# dw1000_schematic.net
KiCad netlist of a schematic drawn in EAGLE
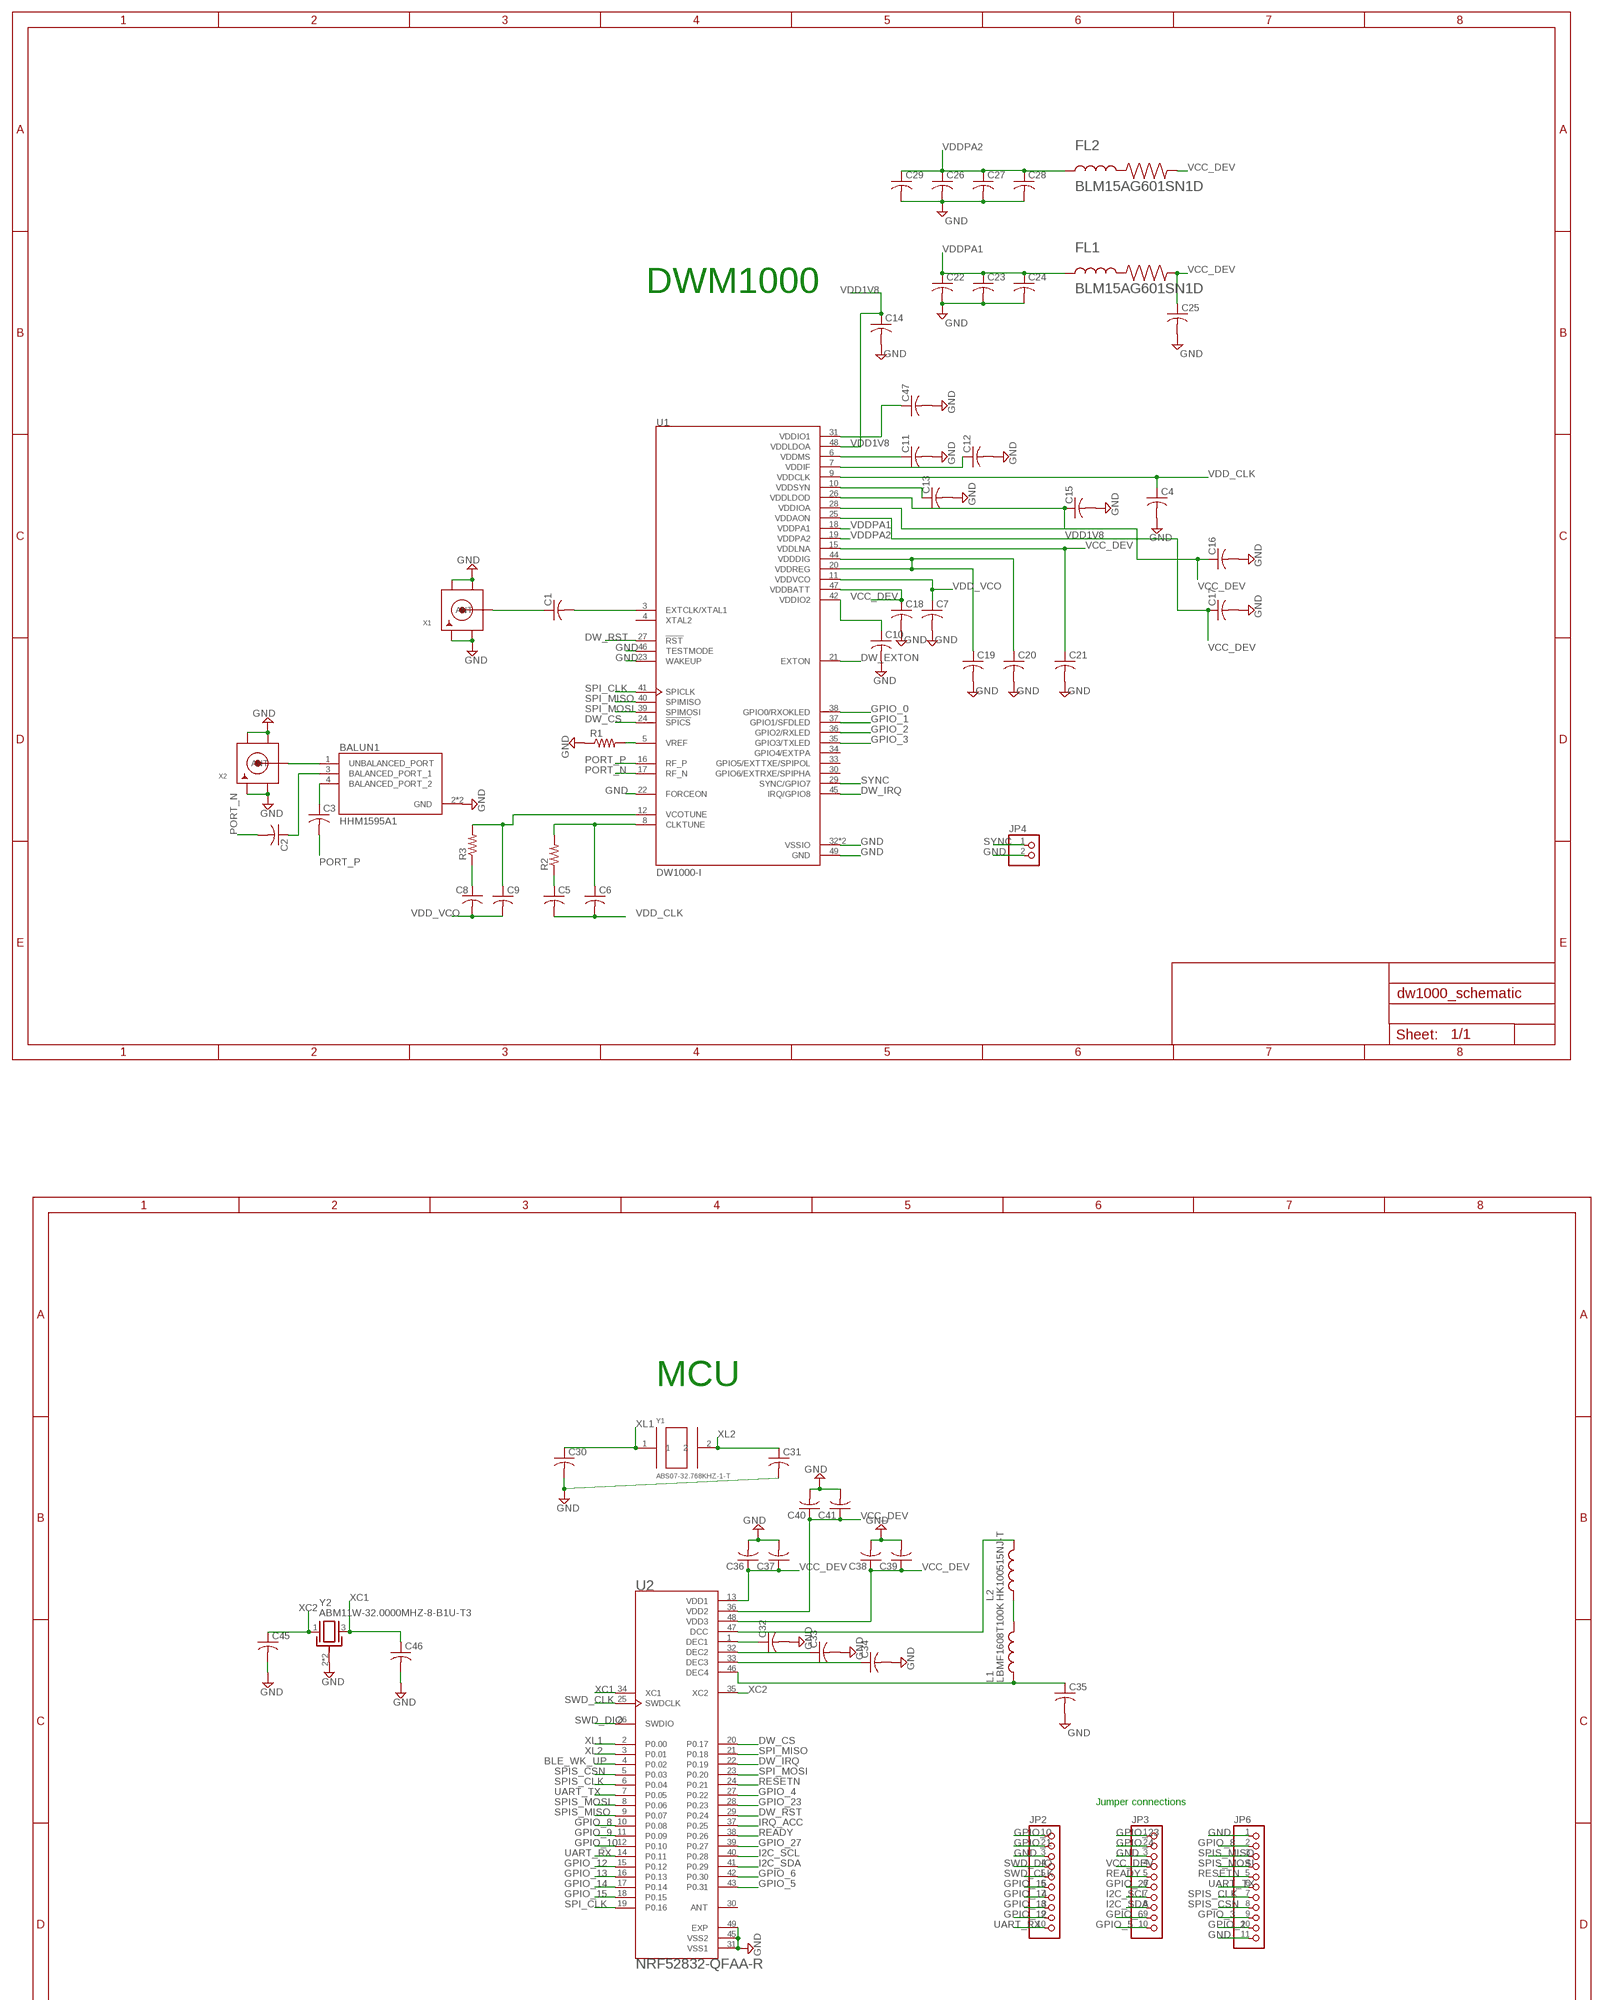
[diagram p0: schematic, sheet 1, part 1 of 2]
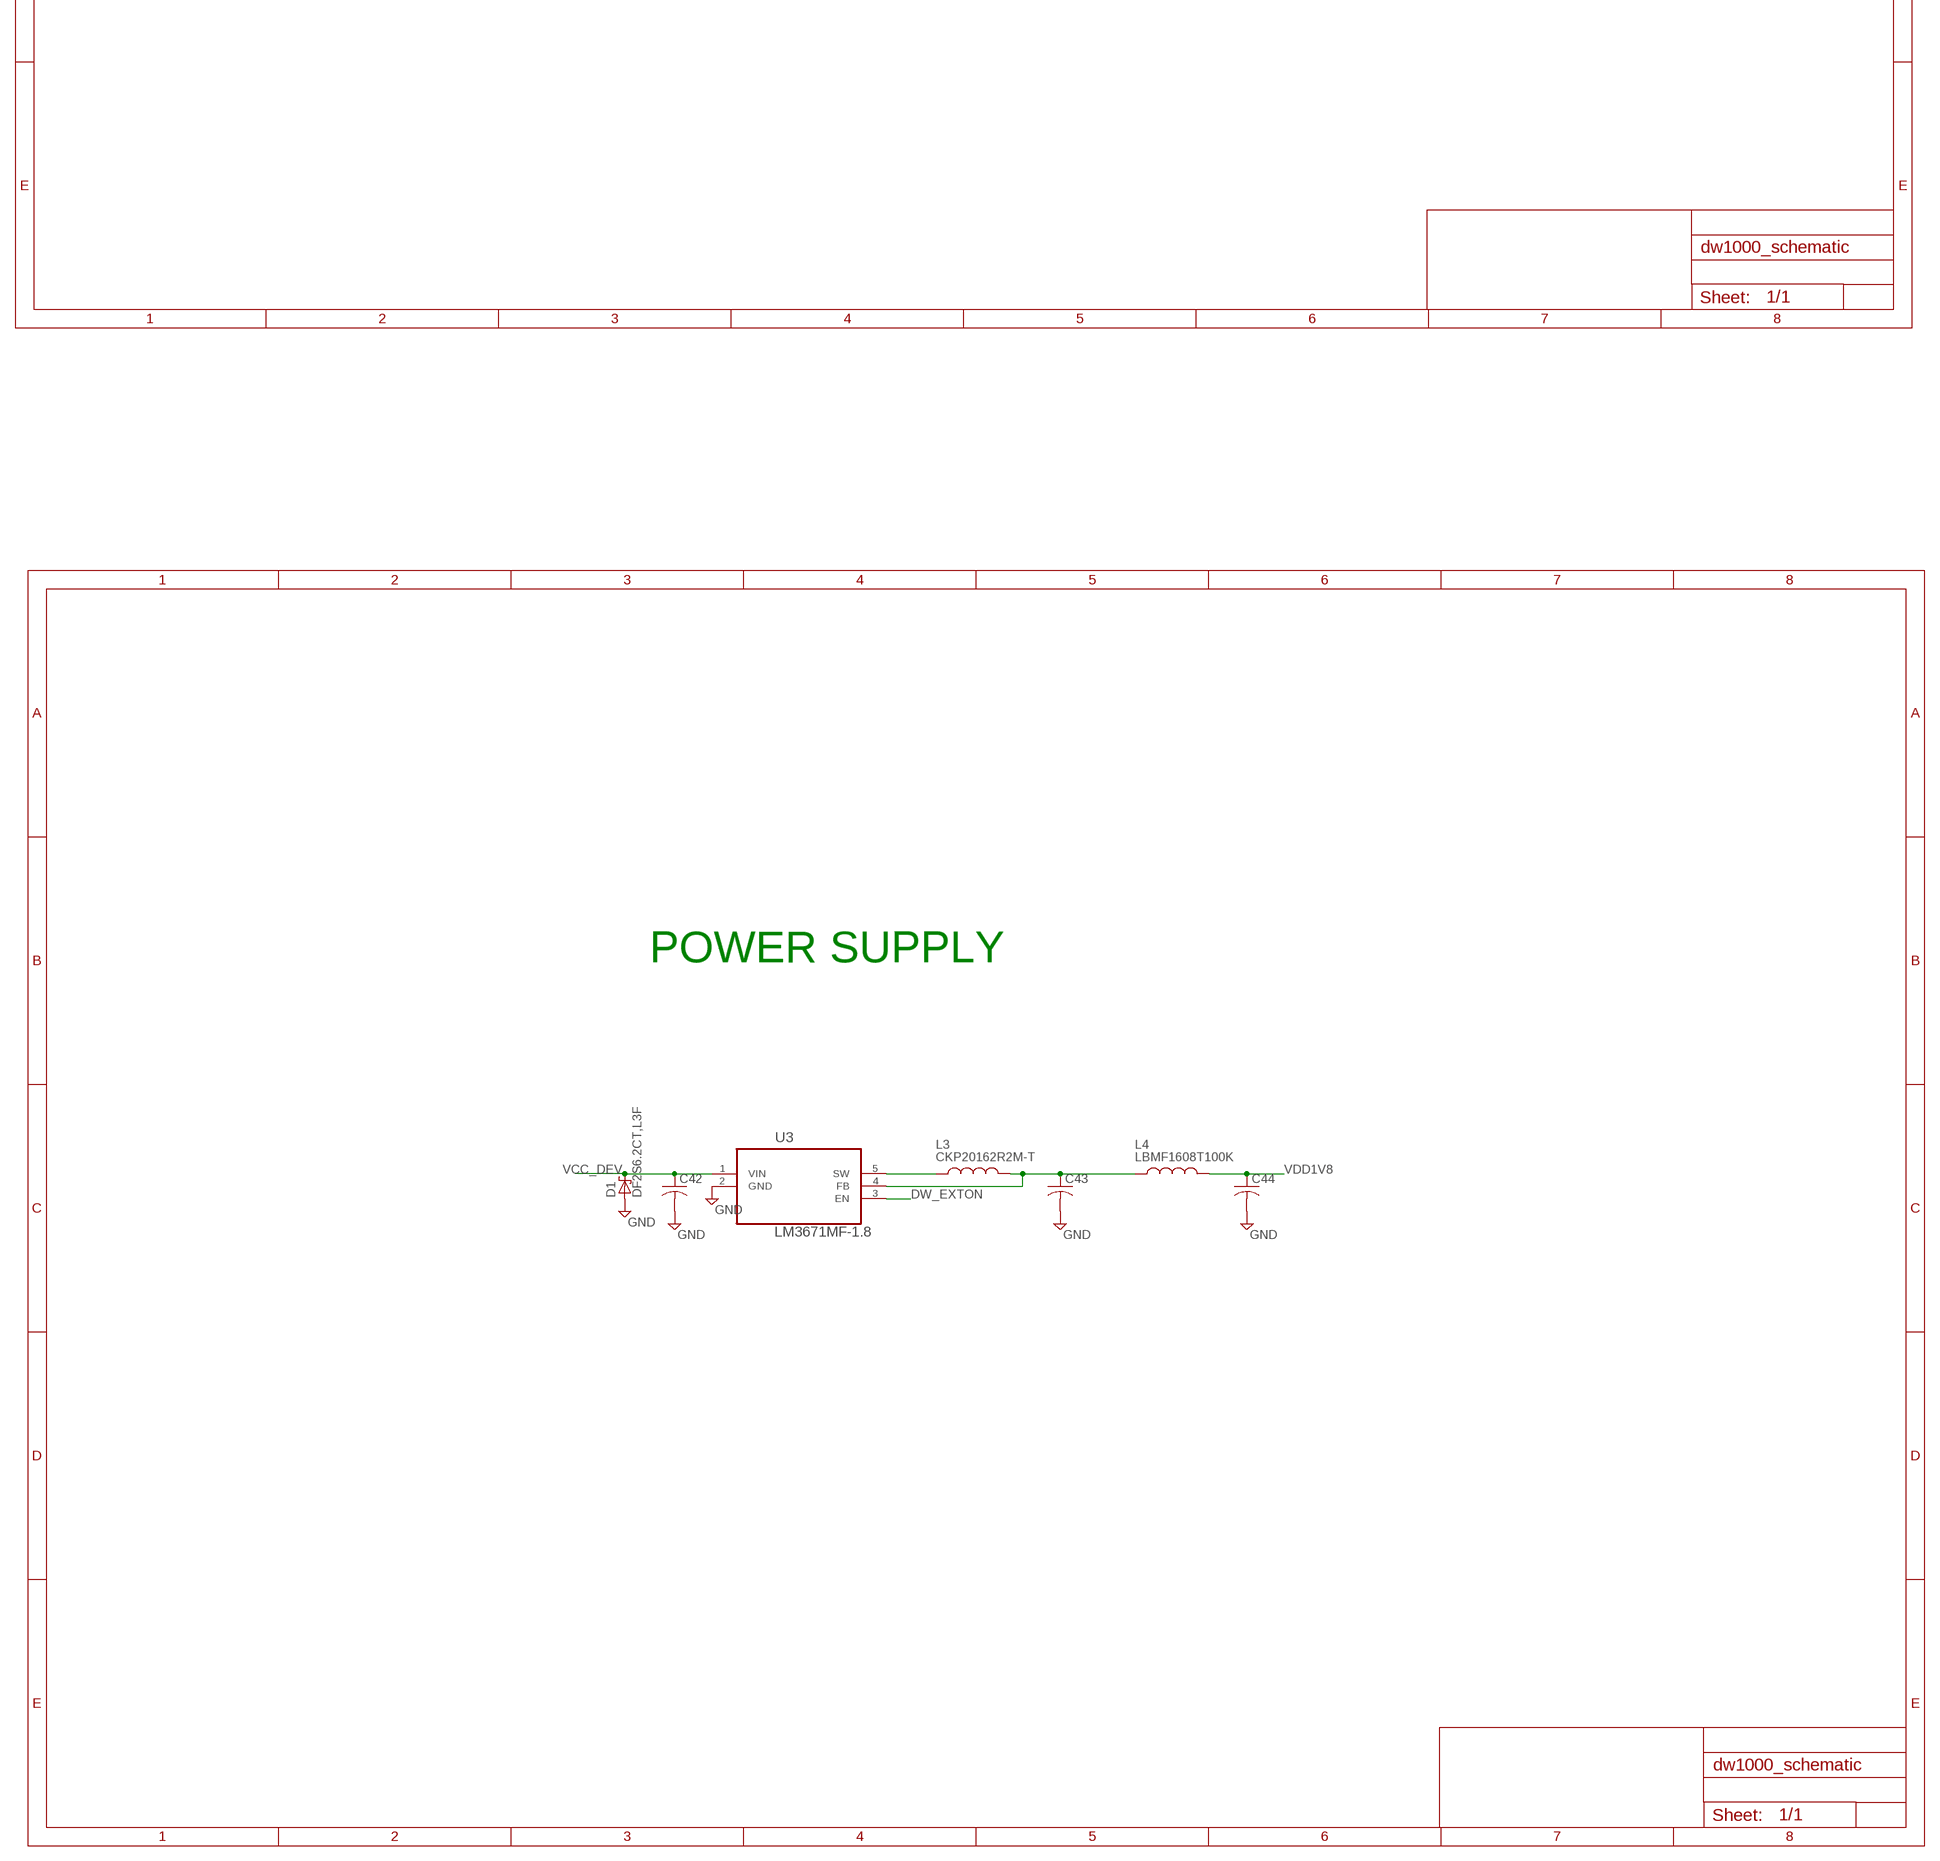
[diagram p1: schematic, sheet 1, part 2 of 2]

(export (version "E")
  (design (tool "Eeschema 10.0.6"))
  (components
    (comp (ref "BALUN1")
      (value "HHM1595A1")
      (footprint "eagle-import:BALUN_HHM1595A1")
      (fields (field (name "MF") "TDK"))
      (libsource (lib "eagle-import") (part "HHM1595A1"))
    )
    (comp (ref "C1")
      (value "C-USC0603K")
      (footprint "eagle-import:C0603K")
      (libsource (lib "eagle-import") (part "C-USC0603K"))
    )
    (comp (ref "C2")
      (value "C-USC0402K")
      (footprint "eagle-import:C0402K")
      (libsource (lib "eagle-import") (part "C-USC0402K"))
    )
    (comp (ref "C3")
      (value "C-USC0402K")
      (footprint "eagle-import:C0402K")
      (libsource (lib "eagle-import") (part "C-USC0402K"))
    )
    (comp (ref "C4")
      (value "C-USC0402K")
      (footprint "eagle-import:C0402K")
      (libsource (lib "eagle-import") (part "C-USC0402K"))
    )
    (comp (ref "C5")
      (value "C-USC0402K")
      (footprint "eagle-import:C0402K")
      (libsource (lib "eagle-import") (part "C-USC0402K"))
    )
    (comp (ref "C6")
      (value "C-USC0402K")
      (footprint "eagle-import:C0402K")
      (libsource (lib "eagle-import") (part "C-USC0402K"))
    )
    (comp (ref "C7")
      (value "C-USC0402K")
      (footprint "eagle-import:C0402K")
      (libsource (lib "eagle-import") (part "C-USC0402K"))
    )
    (comp (ref "C8")
      (value "C-USC0402K")
      (footprint "eagle-import:C0402K")
      (libsource (lib "eagle-import") (part "C-USC0402K"))
    )
    (comp (ref "C9")
      (value "C-USC0402K")
      (footprint "eagle-import:C0402K")
      (libsource (lib "eagle-import") (part "C-USC0402K"))
    )
    (comp (ref "C10")
      (value "C-USC0402K")
      (footprint "eagle-import:C0402K")
      (libsource (lib "eagle-import") (part "C-USC0402K"))
    )
    (comp (ref "C11")
      (value "C-USC0402K")
      (footprint "eagle-import:C0402K")
      (libsource (lib "eagle-import") (part "C-USC0402K"))
    )
    (comp (ref "C12")
      (value "C-USC0402K")
      (footprint "eagle-import:C0402K")
      (libsource (lib "eagle-import") (part "C-USC0402K"))
    )
    (comp (ref "C13")
      (value "C-USC0402K")
      (footprint "eagle-import:C0402K")
      (libsource (lib "eagle-import") (part "C-USC0402K"))
    )
    (comp (ref "C14")
      (value "C-USC0402K")
      (footprint "eagle-import:C0402K")
      (libsource (lib "eagle-import") (part "C-USC0402K"))
    )
    (comp (ref "C15")
      (value "C-USC0402K")
      (footprint "eagle-import:C0402K")
      (libsource (lib "eagle-import") (part "C-USC0402K"))
    )
    (comp (ref "C16")
      (value "C-USC0402K")
      (footprint "eagle-import:C0402K")
      (libsource (lib "eagle-import") (part "C-USC0402K"))
    )
    (comp (ref "C17")
      (value "C-USC0402K")
      (footprint "eagle-import:C0402K")
      (libsource (lib "eagle-import") (part "C-USC0402K"))
    )
    (comp (ref "C18")
      (value "C-USC0402K")
      (footprint "eagle-import:C0402K")
      (libsource (lib "eagle-import") (part "C-USC0402K"))
    )
    (comp (ref "C19")
      (value "C-USC0402K")
      (footprint "eagle-import:C0402K")
      (libsource (lib "eagle-import") (part "C-USC0402K"))
    )
    (comp (ref "C20")
      (value "C-USC0402K")
      (footprint "eagle-import:C0402K")
      (libsource (lib "eagle-import") (part "C-USC0402K"))
    )
    (comp (ref "C21")
      (value "C-USC0402K")
      (footprint "eagle-import:C0402K")
      (libsource (lib "eagle-import") (part "C-USC0402K"))
    )
    (comp (ref "C22")
      (value "C-USC0402K")
      (footprint "eagle-import:C0402K")
      (libsource (lib "eagle-import") (part "C-USC0402K"))
    )
    (comp (ref "C23")
      (value "C-USC0402K")
      (footprint "eagle-import:C0402K")
      (libsource (lib "eagle-import") (part "C-USC0402K"))
    )
    (comp (ref "C24")
      (value "C-USC0402K")
      (footprint "eagle-import:C0402K")
      (libsource (lib "eagle-import") (part "C-USC0402K"))
    )
    (comp (ref "C25")
      (value "C-USC0603K")
      (footprint "eagle-import:C0603K")
      (libsource (lib "eagle-import") (part "C-USC0603K"))
    )
    (comp (ref "C26")
      (value "C-USC0402K")
      (footprint "eagle-import:C0402K")
      (libsource (lib "eagle-import") (part "C-USC0402K"))
    )
    (comp (ref "C27")
      (value "C-USC0402K")
      (footprint "eagle-import:C0402K")
      (libsource (lib "eagle-import") (part "C-USC0402K"))
    )
    (comp (ref "C28")
      (value "C-USC0402K")
      (footprint "eagle-import:C0402K")
      (libsource (lib "eagle-import") (part "C-USC0402K"))
    )
    (comp (ref "C29")
      (value "C-USC0805K")
      (footprint "eagle-import:C0805K")
      (libsource (lib "eagle-import") (part "rcl_334_C-USC0805K"))
    )
    (comp (ref "C30")
      (value "C-USC0402K")
      (footprint "eagle-import:C0402K")
      (libsource (lib "eagle-import") (part "C-USC0402K"))
    )
    (comp (ref "C31")
      (value "C-USC0402K")
      (footprint "eagle-import:C0402K")
      (libsource (lib "eagle-import") (part "C-USC0402K"))
    )
    (comp (ref "C32")
      (value "C-USC0402K")
      (footprint "eagle-import:C0402K")
      (libsource (lib "eagle-import") (part "C-USC0402K"))
    )
    (comp (ref "C33")
      (value "C-USC0402K")
      (footprint "eagle-import:C0402K")
      (libsource (lib "eagle-import") (part "C-USC0402K"))
    )
    (comp (ref "C34")
      (value "C-USC0402K")
      (footprint "eagle-import:C0402K")
      (libsource (lib "eagle-import") (part "C-USC0402K"))
    )
    (comp (ref "C35")
      (value "C-USC0603K")
      (footprint "eagle-import:C0603K")
      (libsource (lib "eagle-import") (part "C-USC0603K"))
    )
    (comp (ref "C36")
      (value "C-USC0402K")
      (footprint "eagle-import:C0402K")
      (libsource (lib "eagle-import") (part "C-USC0402K"))
    )
    (comp (ref "C37")
      (value "C-USC0402K")
      (footprint "eagle-import:C0402K")
      (libsource (lib "eagle-import") (part "C-USC0402K"))
    )
    (comp (ref "C38")
      (value "C-USC0603K")
      (footprint "eagle-import:C0603K")
      (libsource (lib "eagle-import") (part "C-USC0603K"))
    )
    (comp (ref "C39")
      (value "C-USC0402K")
      (footprint "eagle-import:C0402K")
      (libsource (lib "eagle-import") (part "C-USC0402K"))
    )
    (comp (ref "C40")
      (value "C-USC0402K")
      (footprint "eagle-import:C0402K")
      (libsource (lib "eagle-import") (part "C-USC0402K"))
    )
    (comp (ref "C41")
      (value "C-USC0402K")
      (footprint "eagle-import:C0402K")
      (libsource (lib "eagle-import") (part "C-USC0402K"))
    )
    (comp (ref "C42")
      (value "C-USC0603K")
      (footprint "eagle-import:C0603K")
      (libsource (lib "eagle-import") (part "C-USC0603K"))
    )
    (comp (ref "C43")
      (value "C-USC0603K")
      (footprint "eagle-import:C0603K")
      (libsource (lib "eagle-import") (part "C-USC0603K"))
    )
    (comp (ref "C44")
      (value "C-USC0603K")
      (footprint "eagle-import:C0603K")
      (libsource (lib "eagle-import") (part "C-USC0603K"))
    )
    (comp (ref "C45")
      (value "C-USC0402K")
      (footprint "eagle-import:C0402K")
      (libsource (lib "eagle-import") (part "C-USC0402K"))
    )
    (comp (ref "C46")
      (value "C-USC0402K")
      (footprint "eagle-import:C0402K")
      (libsource (lib "eagle-import") (part "C-USC0402K"))
    )
    (comp (ref "C47")
      (value "C-USC0402K")
      (footprint "eagle-import:C0402K")
      (libsource (lib "eagle-import") (part "C-USC0402K"))
    )
    (comp (ref "D1")
      (value "DF2S6.2CT,L3F")
      (footprint "eagle-import:DF2S6.2CT,L3F")
      (libsource (lib "eagle-import") (part "DF2S6.2CT,L3F"))
    )
    (comp (ref "FL1")
      (value "BLM15AG601SN1D")
      (footprint "eagle-import:BEADC1005X55N")
      (fields (field (name "MF") "Murata"))
      (libsource (lib "eagle-import") (part "BLM15AG601SN1D"))
    )
    (comp (ref "FL2")
      (value "BLM15AG601SN1D")
      (footprint "eagle-import:BEADC1005X55N")
      (fields (field (name "MF") "Murata"))
      (libsource (lib "eagle-import") (part "BLM15AG601SN1D"))
    )
    (comp (ref "JP2")
      (value "PINHD-1X10")
      (footprint "eagle-import:1X10")
      (libsource (lib "eagle-import") (part "PINHD-1X10"))
    )
    (comp (ref "JP3")
      (value "PINHD-1X10")
      (footprint "eagle-import:1X10")
      (libsource (lib "eagle-import") (part "PINHD-1X10"))
    )
    (comp (ref "JP4")
      (value "PINHD-1X2")
      (footprint "eagle-import:1X02")
      (libsource (lib "eagle-import") (part "PINHD-1X2"))
    )
    (comp (ref "JP6")
      (value "PINHD-1X11")
      (footprint "eagle-import:1X11")
      (libsource (lib "eagle-import") (part "PINHD-1X11"))
    )
    (comp (ref "L1")
      (value "LBMF1608T100K")
      (footprint "eagle-import:INDC1608X100N")
      (fields (field (name "MF") "Taiyo Yuden"))
      (libsource (lib "eagle-import") (part "LBMF1608T100K"))
    )
    (comp (ref "L2")
      (value "HK100515NJ-T")
      (footprint "eagle-import:INDC1005X55N")
      (fields (field (name "MF") "Taiyo Yuden"))
      (libsource (lib "eagle-import") (part "HK100515NJ-T"))
    )
    (comp (ref "L3")
      (value "CKP20162R2M-T")
      (footprint "eagle-import:INDC2016X100N")
      (fields (field (name "MF") "Taiyo Yuden"))
      (libsource (lib "eagle-import") (part "CKP20162R2M-T"))
    )
    (comp (ref "L4")
      (value "LBMF1608T100K")
      (footprint "eagle-import:INDC1608X100N")
      (fields (field (name "MF") "Taiyo Yuden"))
      (libsource (lib "eagle-import") (part "LBMF1608T100K"))
    )
    (comp (ref "R1")
      (value "R-US_R0402")
      (footprint "eagle-import:R0402")
      (libsource (lib "eagle-import") (part "R-US_R0402"))
    )
    (comp (ref "R2")
      (value "R-US_R0402")
      (footprint "eagle-import:R0402")
      (libsource (lib "eagle-import") (part "R-US_R0402"))
    )
    (comp (ref "R3")
      (value "R-US_R0402")
      (footprint "eagle-import:R0402")
      (libsource (lib "eagle-import") (part "R-US_R0402"))
    )
    (comp (ref "U1")
      (value "DW1000-I")
      (footprint "eagle-import:QFN40P600X600X90-49N")
      (fields (field (name "MF") "Decawave Limited"))
      (libsource (lib "eagle-import") (part "DW1000-I"))
    )
    (comp (ref "U2")
      (value "NRF52832-QFAA-R")
      (footprint "eagle-import:QFN40P600X600X90-49N")
      (fields (field (name "MF") "Nordic"))
      (libsource (lib "eagle-import") (part "NRF52832-QFAA-R"))
    )
    (comp (ref "U3")
      (value "LM3671MF-1.8")
      (footprint "eagle-import:SOT95P284X122-5N")
      (fields (field (name "MF") "Texas Instruments") (field (name "MP") "LM3671MF-1.8/NOPB"))
      (libsource (lib "eagle-import") (part "LM3671MF-1.8"))
    )
    (comp (ref "X1")
      (value "SMACONNECTOR_EDGE")
      (footprint "eagle-import:SMA_EDGELAUNCH")
      (libsource (lib "eagle-import") (part "SMACONNECTOR_EDGE"))
    )
    (comp (ref "X2")
      (value "SMACONNECTOR_EDGE")
      (footprint "eagle-import:SMA_EDGELAUNCH")
      (libsource (lib "eagle-import") (part "SMACONNECTOR_EDGE"))
    )
    (comp (ref "Y1")
      (value "ABS07-32.768KHZ-1-T")
      (footprint "eagle-import:XTAL320X150X90")
      (fields (field (name "MF") "Abracon"))
      (libsource (lib "eagle-import") (part "ABS07-32.768KHZ-1-T"))
    )
    (comp (ref "Y2")
      (value "ABM11W-32.0000MHZ-8-B1U-T3")
      (footprint "eagle-import:XTAL_ABM11W-32.0000MHZ-8-B1U-T3")
      (fields (field (name "MF") "Abracon LLC"))
      (libsource (lib "eagle-import") (part "ABM11W-32.0000MHZ-8-B1U-T3"))
    )
  )
  (nets
    (net (code "1") (name "/BLE_WK_UP") (class "Default")
      (node (ref "U2") (pin "4") (pinfunction "P0.02_4") (pintype "bidirectional"))
    )
    (net (code "2") (name "/DW_CS") (class "Default")
      (node (ref "U1") (pin "24") (pinfunction "~{SPICS}_24") (pintype "input"))
      (node (ref "U2") (pin "20") (pinfunction "P0.17_20") (pintype "bidirectional"))
    )
    (net (code "3") (name "/DW_EXTON") (class "Default")
      (node (ref "U1") (pin "21") (pinfunction "EXTON_21") (pintype "output"))
      (node (ref "U3") (pin "3") (pinfunction "EN_3") (pintype "passive"))
    )
    (net (code "4") (name "/DW_IRQ") (class "Default")
      (node (ref "U1") (pin "45") (pinfunction "IRQ/GPIO8_45") (pintype "bidirectional"))
      (node (ref "U2") (pin "22") (pinfunction "P0.19_22") (pintype "bidirectional"))
    )
    (net (code "5") (name "/DW_RST") (class "Default")
      (node (ref "U1") (pin "27") (pinfunction "~{RST}_27") (pintype "bidirectional"))
      (node (ref "U2") (pin "29") (pinfunction "P0.24_29") (pintype "bidirectional"))
    )
    (net (code "6") (name "/GPIO_0") (class "Default")
      (node (ref "JP2") (pin "1") (pinfunction "1_1") (pintype "passive"))
      (node (ref "U1") (pin "38") (pinfunction "GPIO0/RXOKLED_38") (pintype "bidirectional"))
    )
    (net (code "7") (name "/GPIO_1") (class "Default")
      (node (ref "JP2") (pin "2") (pinfunction "2_2") (pintype "passive"))
      (node (ref "U1") (pin "37") (pinfunction "GPIO1/SFDLED_37") (pintype "bidirectional"))
    )
    (net (code "8") (name "/GPIO_2") (class "Default")
      (node (ref "JP6") (pin "10") (pinfunction "10_10") (pintype "passive"))
      (node (ref "U1") (pin "36") (pinfunction "GPIO2/RXLED_36") (pintype "bidirectional"))
    )
    (net (code "9") (name "/GPIO_3") (class "Default")
      (node (ref "JP6") (pin "9") (pinfunction "9_9") (pintype "passive"))
      (node (ref "U1") (pin "35") (pinfunction "GPIO3/TXLED_35") (pintype "bidirectional"))
    )
    (net (code "10") (name "/GPIO_4") (class "Default")
      (node (ref "JP3") (pin "2") (pinfunction "2_2") (pintype "passive"))
      (node (ref "U2") (pin "27") (pinfunction "P0.22_27") (pintype "bidirectional"))
    )
    (net (code "11") (name "/GPIO_5") (class "Default")
      (node (ref "JP3") (pin "10") (pinfunction "10_10") (pintype "passive"))
      (node (ref "U2") (pin "43") (pinfunction "P0.31_43") (pintype "bidirectional"))
    )
    (net (code "12") (name "/GPIO_6") (class "Default")
      (node (ref "JP3") (pin "9") (pinfunction "9_9") (pintype "passive"))
      (node (ref "U2") (pin "42") (pinfunction "P0.30_42") (pintype "bidirectional"))
    )
    (net (code "13") (name "/GPIO_8") (class "Default")
      (node (ref "JP6") (pin "2") (pinfunction "2_2") (pintype "passive"))
      (node (ref "U2") (pin "10") (pinfunction "P0.08_10") (pintype "bidirectional"))
    )
    (net (code "14") (name "/GPIO_9") (class "Default")
      (node (ref "U2") (pin "11") (pinfunction "P0.09_11") (pintype "bidirectional"))
    )
    (net (code "15") (name "/GPIO_10") (class "Default")
      (node (ref "U2") (pin "12") (pinfunction "P0.10_12") (pintype "bidirectional"))
    )
    (net (code "16") (name "/GPIO_12") (class "Default")
      (node (ref "JP2") (pin "9") (pinfunction "9_9") (pintype "passive"))
      (node (ref "U2") (pin "15") (pinfunction "P0.12_15") (pintype "bidirectional"))
    )
    (net (code "17") (name "/GPIO_13") (class "Default")
      (node (ref "JP2") (pin "8") (pinfunction "8_8") (pintype "passive"))
      (node (ref "U2") (pin "16") (pinfunction "P0.13_16") (pintype "bidirectional"))
    )
    (net (code "18") (name "/GPIO_14") (class "Default")
      (node (ref "JP2") (pin "7") (pinfunction "7_7") (pintype "passive"))
      (node (ref "U2") (pin "17") (pinfunction "P0.14_17") (pintype "bidirectional"))
    )
    (net (code "19") (name "/GPIO_15") (class "Default")
      (node (ref "JP2") (pin "6") (pinfunction "6_6") (pintype "passive"))
      (node (ref "U2") (pin "18") (pinfunction "P0.15_18") (pintype "bidirectional"))
    )
    (net (code "20") (name "/GPIO_23") (class "Default")
      (node (ref "JP3") (pin "1") (pinfunction "1_1") (pintype "passive"))
      (node (ref "U2") (pin "28") (pinfunction "P0.23_28") (pintype "bidirectional"))
    )
    (net (code "21") (name "/GPIO_27") (class "Default")
      (node (ref "JP3") (pin "6") (pinfunction "6_6") (pintype "passive"))
      (node (ref "U2") (pin "39") (pinfunction "P0.27_39") (pintype "bidirectional"))
    )
    (net (code "22") (name "/I2C_SCL") (class "Default")
      (node (ref "JP3") (pin "7") (pinfunction "7_7") (pintype "passive"))
      (node (ref "U2") (pin "40") (pinfunction "P0.28_40") (pintype "bidirectional"))
    )
    (net (code "23") (name "/I2C_SDA") (class "Default")
      (node (ref "JP3") (pin "8") (pinfunction "8_8") (pintype "passive"))
      (node (ref "U2") (pin "41") (pinfunction "P0.29_41") (pintype "bidirectional"))
    )
    (net (code "24") (name "/IRQ_ACC") (class "Default")
      (node (ref "U2") (pin "37") (pinfunction "P0.25_37") (pintype "bidirectional"))
    )
    (net (code "25") (name "/PORT_N") (class "Default")
      (node (ref "C2") (pin "2") (pinfunction "2_2") (pintype "passive"))
      (node (ref "U1") (pin "17") (pinfunction "RF_N_17") (pintype "bidirectional"))
    )
    (net (code "26") (name "/PORT_P") (class "Default")
      (node (ref "C3") (pin "2") (pinfunction "2_2") (pintype "passive"))
      (node (ref "U1") (pin "16") (pinfunction "RF_P_16") (pintype "bidirectional"))
    )
    (net (code "27") (name "/READY") (class "Default")
      (node (ref "JP3") (pin "5") (pinfunction "5_5") (pintype "passive"))
      (node (ref "U2") (pin "38") (pinfunction "P0.26_38") (pintype "bidirectional"))
    )
    (net (code "28") (name "/RESETN") (class "Default")
      (node (ref "JP6") (pin "5") (pinfunction "5_5") (pintype "passive"))
      (node (ref "U2") (pin "24") (pinfunction "P0.21_24") (pintype "bidirectional"))
    )
    (net (code "29") (name "/SPIS_CLK") (class "Default")
      (node (ref "JP6") (pin "7") (pinfunction "7_7") (pintype "passive"))
      (node (ref "U2") (pin "6") (pinfunction "P0.04_6") (pintype "bidirectional"))
    )
    (net (code "30") (name "/SPIS_CSN") (class "Default")
      (node (ref "JP6") (pin "8") (pinfunction "8_8") (pintype "passive"))
      (node (ref "U2") (pin "5") (pinfunction "P0.03_5") (pintype "bidirectional"))
    )
    (net (code "31") (name "/SPIS_MISO") (class "Default")
      (node (ref "JP6") (pin "3") (pinfunction "3_3") (pintype "passive"))
      (node (ref "U2") (pin "9") (pinfunction "P0.07_9") (pintype "bidirectional"))
    )
    (net (code "32") (name "/SPIS_MOSI") (class "Default")
      (node (ref "JP6") (pin "4") (pinfunction "4_4") (pintype "passive"))
      (node (ref "U2") (pin "8") (pinfunction "P0.06_8") (pintype "bidirectional"))
    )
    (net (code "33") (name "/SPI_CLK") (class "Default")
      (node (ref "U1") (pin "41") (pinfunction "SPICLK_41") (pintype "input"))
      (node (ref "U2") (pin "19") (pinfunction "P0.16_19") (pintype "bidirectional"))
    )
    (net (code "34") (name "/SPI_MISO") (class "Default")
      (node (ref "U1") (pin "40") (pinfunction "SPIMISO_40") (pintype "output"))
      (node (ref "U2") (pin "21") (pinfunction "P0.18_21") (pintype "bidirectional"))
    )
    (net (code "35") (name "/SPI_MOSI") (class "Default")
      (node (ref "U1") (pin "39") (pinfunction "SPIMOSI_39") (pintype "input"))
      (node (ref "U2") (pin "23") (pinfunction "P0.20_23") (pintype "bidirectional"))
    )
    (net (code "36") (name "/SWD_CLK") (class "Default")
      (node (ref "JP2") (pin "5") (pinfunction "5_5") (pintype "passive"))
      (node (ref "U2") (pin "25") (pinfunction "SWDCLK_25") (pintype "input"))
    )
    (net (code "37") (name "/SWD_DIO") (class "Default")
      (node (ref "JP2") (pin "4") (pinfunction "4_4") (pintype "passive"))
      (node (ref "U2") (pin "26") (pinfunction "SWDIO_26") (pintype "bidirectional"))
    )
    (net (code "38") (name "/SYNC") (class "Default")
      (node (ref "JP4") (pin "1") (pinfunction "1_1") (pintype "passive"))
      (node (ref "U1") (pin "29") (pinfunction "SYNC/GPIO7_29") (pintype "bidirectional"))
    )
    (net (code "39") (name "/UART_RX") (class "Default")
      (node (ref "JP2") (pin "10") (pinfunction "10_10") (pintype "passive"))
      (node (ref "U2") (pin "14") (pinfunction "P0.11_14") (pintype "bidirectional"))
    )
    (net (code "40") (name "/UART_TX") (class "Default")
      (node (ref "JP6") (pin "6") (pinfunction "6_6") (pintype "passive"))
      (node (ref "U2") (pin "7") (pinfunction "P0.05_7") (pintype "bidirectional"))
    )
    (net (code "41") (name "/VCC_DEV") (class "Default")
      (node (ref "C16") (pin "1") (pinfunction "1_1") (pintype "passive"))
      (node (ref "C17") (pin "1") (pinfunction "1_1") (pintype "passive"))
      (node (ref "C18") (pin "1") (pinfunction "1_1") (pintype "passive"))
      (node (ref "C21") (pin "1") (pinfunction "1_1") (pintype "passive"))
      (node (ref "C25") (pin "1") (pinfunction "1_1") (pintype "passive"))
      (node (ref "C36") (pin "1") (pinfunction "1_1") (pintype "passive"))
      (node (ref "C37") (pin "1") (pinfunction "1_1") (pintype "passive"))
      (node (ref "C38") (pin "1") (pinfunction "1_1") (pintype "passive"))
      (node (ref "C39") (pin "1") (pinfunction "1_1") (pintype "passive"))
      (node (ref "C40") (pin "1") (pinfunction "1_1") (pintype "passive"))
      (node (ref "C41") (pin "1") (pinfunction "1_1") (pintype "passive"))
      (node (ref "C42") (pin "1") (pinfunction "1_1") (pintype "passive"))
      (node (ref "D1") (pin "2") (pinfunction "2_2") (pintype "passive"))
      (node (ref "FL1") (pin "2") (pinfunction "2_2") (pintype "passive"))
      (node (ref "FL2") (pin "2") (pinfunction "2_2") (pintype "passive"))
      (node (ref "JP3") (pin "4") (pinfunction "4_4") (pintype "passive"))
      (node (ref "U1") (pin "15") (pinfunction "VDDLNA_15") (pintype "power_in"))
      (node (ref "U1") (pin "25") (pinfunction "VDDAON_25") (pintype "power_in"))
      (node (ref "U1") (pin "28") (pinfunction "VDDIOA_28") (pintype "power_in"))
      (node (ref "U1") (pin "47") (pinfunction "VDDBATT_47") (pintype "power_in"))
      (node (ref "U2") (pin "13") (pinfunction "VDD1_13") (pintype "power_in"))
      (node (ref "U2") (pin "36") (pinfunction "VDD2_36") (pintype "power_in"))
      (node (ref "U2") (pin "48") (pinfunction "VDD3_48") (pintype "power_in"))
      (node (ref "U3") (pin "1") (pinfunction "VIN_1") (pintype "input"))
    )
    (net (code "42") (name "/VDD1V8") (class "Default")
      (node (ref "C14") (pin "1") (pinfunction "1_1") (pintype "passive"))
      (node (ref "C15") (pin "1") (pinfunction "1_1") (pintype "passive"))
      (node (ref "C44") (pin "1") (pinfunction "1_1") (pintype "passive"))
      (node (ref "L4") (pin "2") (pinfunction "2_2") (pintype "passive"))
      (node (ref "U1") (pin "26") (pinfunction "VDDLDOD_26") (pintype "power_in"))
      (node (ref "U1") (pin "48") (pinfunction "VDDLDOA_48") (pintype "power_in"))
    )
    (net (code "43") (name "/VDDPA1") (class "Default")
      (node (ref "C22") (pin "1") (pinfunction "1_1") (pintype "passive"))
      (node (ref "C23") (pin "1") (pinfunction "1_1") (pintype "passive"))
      (node (ref "C24") (pin "1") (pinfunction "1_1") (pintype "passive"))
      (node (ref "FL1") (pin "1") (pinfunction "1_1") (pintype "passive"))
      (node (ref "U1") (pin "18") (pinfunction "VDDPA1_18") (pintype "power_in"))
    )
    (net (code "44") (name "/VDDPA2") (class "Default")
      (node (ref "C26") (pin "1") (pinfunction "1_1") (pintype "passive"))
      (node (ref "C27") (pin "1") (pinfunction "1_1") (pintype "passive"))
      (node (ref "C28") (pin "1") (pinfunction "1_1") (pintype "passive"))
      (node (ref "C29") (pin "1") (pinfunction "1_1") (pintype "passive"))
      (node (ref "FL2") (pin "1") (pinfunction "1_1") (pintype "passive"))
      (node (ref "U1") (pin "19") (pinfunction "VDDPA2_19") (pintype "power_in"))
    )
    (net (code "45") (name "/VDD_CLK") (class "Default")
      (node (ref "C4") (pin "1") (pinfunction "1_1") (pintype "passive"))
      (node (ref "C5") (pin "2") (pinfunction "2_2") (pintype "passive"))
      (node (ref "C6") (pin "2") (pinfunction "2_2") (pintype "passive"))
      (node (ref "U1") (pin "9") (pinfunction "VDDCLK_9") (pintype "power_in"))
    )
    (net (code "46") (name "/VDD_VCO") (class "Default")
      (node (ref "C7") (pin "1") (pinfunction "1_1") (pintype "passive"))
      (node (ref "C8") (pin "2") (pinfunction "2_2") (pintype "passive"))
      (node (ref "C9") (pin "2") (pinfunction "2_2") (pintype "passive"))
      (node (ref "U1") (pin "11") (pinfunction "VDDVCO_11") (pintype "power_in"))
    )
    (net (code "47") (name "/XC1") (class "Default")
      (node (ref "C46") (pin "1") (pinfunction "1_1") (pintype "passive"))
      (node (ref "U2") (pin "34") (pinfunction "XC1_34") (pintype "input"))
      (node (ref "Y2") (pin "3") (pinfunction "3_3") (pintype "passive"))
    )
    (net (code "48") (name "/XC2") (class "Default")
      (node (ref "C45") (pin "1") (pinfunction "1_1") (pintype "passive"))
      (node (ref "U2") (pin "35") (pinfunction "XC2_35") (pintype "output"))
      (node (ref "Y2") (pin "1") (pinfunction "1_1") (pintype "passive"))
    )
    (net (code "49") (name "/XL1") (class "Default")
      (node (ref "C30") (pin "1") (pinfunction "1_1") (pintype "passive"))
      (node (ref "U2") (pin "2") (pinfunction "P0.00_2") (pintype "bidirectional"))
      (node (ref "Y1") (pin "1") (pinfunction "1_1") (pintype "passive"))
    )
    (net (code "50") (name "/XL2") (class "Default")
      (node (ref "C31") (pin "1") (pinfunction "1_1") (pintype "passive"))
      (node (ref "U2") (pin "3") (pinfunction "P0.01_3") (pintype "bidirectional"))
      (node (ref "Y1") (pin "2") (pinfunction "2_2") (pintype "passive"))
    )
    (net (code "51") (name "GND") (class "Default")
      (node (ref "BALUN1") (pin "2") (pinfunction "GND_2") (pintype "power_in"))
      (node (ref "BALUN1") (pin "5") (pinfunction "GND_5") (pintype "power_in"))
      (node (ref "C10") (pin "2") (pinfunction "2_2") (pintype "passive"))
      (node (ref "C11") (pin "2") (pinfunction "2_2") (pintype "passive"))
      (node (ref "C12") (pin "2") (pinfunction "2_2") (pintype "passive"))
      (node (ref "C13") (pin "2") (pinfunction "2_2") (pintype "passive"))
      (node (ref "C14") (pin "2") (pinfunction "2_2") (pintype "passive"))
      (node (ref "C15") (pin "2") (pinfunction "2_2") (pintype "passive"))
      (node (ref "C16") (pin "2") (pinfunction "2_2") (pintype "passive"))
      (node (ref "C17") (pin "2") (pinfunction "2_2") (pintype "passive"))
      (node (ref "C18") (pin "2") (pinfunction "2_2") (pintype "passive"))
      (node (ref "C19") (pin "2") (pinfunction "2_2") (pintype "passive"))
      (node (ref "C20") (pin "2") (pinfunction "2_2") (pintype "passive"))
      (node (ref "C21") (pin "2") (pinfunction "2_2") (pintype "passive"))
      (node (ref "C22") (pin "2") (pinfunction "2_2") (pintype "passive"))
      (node (ref "C23") (pin "2") (pinfunction "2_2") (pintype "passive"))
      (node (ref "C24") (pin "2") (pinfunction "2_2") (pintype "passive"))
      (node (ref "C25") (pin "2") (pinfunction "2_2") (pintype "passive"))
      (node (ref "C26") (pin "2") (pinfunction "2_2") (pintype "passive"))
      (node (ref "C27") (pin "2") (pinfunction "2_2") (pintype "passive"))
      (node (ref "C28") (pin "2") (pinfunction "2_2") (pintype "passive"))
      (node (ref "C29") (pin "2") (pinfunction "2_2") (pintype "passive"))
      (node (ref "C30") (pin "2") (pinfunction "2_2") (pintype "passive"))
      (node (ref "C31") (pin "2") (pinfunction "2_2") (pintype "passive"))
      (node (ref "C32") (pin "2") (pinfunction "2_2") (pintype "passive"))
      (node (ref "C33") (pin "2") (pinfunction "2_2") (pintype "passive"))
      (node (ref "C34") (pin "2") (pinfunction "2_2") (pintype "passive"))
      (node (ref "C35") (pin "2") (pinfunction "2_2") (pintype "passive"))
      (node (ref "C36") (pin "2") (pinfunction "2_2") (pintype "passive"))
      (node (ref "C37") (pin "2") (pinfunction "2_2") (pintype "passive"))
      (node (ref "C38") (pin "2") (pinfunction "2_2") (pintype "passive"))
      (node (ref "C39") (pin "2") (pinfunction "2_2") (pintype "passive"))
      (node (ref "C4") (pin "2") (pinfunction "2_2") (pintype "passive"))
      (node (ref "C40") (pin "2") (pinfunction "2_2") (pintype "passive"))
      (node (ref "C41") (pin "2") (pinfunction "2_2") (pintype "passive"))
      (node (ref "C42") (pin "2") (pinfunction "2_2") (pintype "passive"))
      (node (ref "C43") (pin "2") (pinfunction "2_2") (pintype "passive"))
      (node (ref "C44") (pin "2") (pinfunction "2_2") (pintype "passive"))
      (node (ref "C45") (pin "2") (pinfunction "2_2") (pintype "passive"))
      (node (ref "C46") (pin "2") (pinfunction "2_2") (pintype "passive"))
      (node (ref "C47") (pin "2") (pinfunction "2_2") (pintype "passive"))
      (node (ref "C7") (pin "2") (pinfunction "2_2") (pintype "passive"))
      (node (ref "D1") (pin "1") (pinfunction "1_1") (pintype "passive"))
      (node (ref "JP2") (pin "3") (pinfunction "3_3") (pintype "passive"))
      (node (ref "JP3") (pin "3") (pinfunction "3_3") (pintype "passive"))
      (node (ref "JP4") (pin "2") (pinfunction "2_2") (pintype "passive"))
      (node (ref "JP6") (pin "1") (pinfunction "1_1") (pintype "passive"))
      (node (ref "JP6") (pin "11") (pinfunction "11_11") (pintype "passive"))
      (node (ref "R1") (pin "1") (pinfunction "1_1") (pintype "passive"))
      (node (ref "U1") (pin "22") (pinfunction "FORCEON_22") (pintype "bidirectional"))
      (node (ref "U1") (pin "23") (pinfunction "WAKEUP_23") (pintype "input"))
      (node (ref "U1") (pin "32") (pinfunction "VSSIO_32") (pintype "power_in"))
      (node (ref "U1") (pin "43") (pinfunction "VSSIO_43") (pintype "power_in"))
      (node (ref "U1") (pin "46") (pinfunction "TESTMODE_46") (pintype "input"))
      (node (ref "U1") (pin "49") (pinfunction "GND_49") (pintype "power_in"))
      (node (ref "U2") (pin "31") (pinfunction "VSS1_31") (pintype "power_in"))
      (node (ref "U2") (pin "45") (pinfunction "VSS2_45") (pintype "power_in"))
      (node (ref "U2") (pin "49") (pinfunction "EXP_49") (pintype "power_in"))
      (node (ref "U3") (pin "2") (pinfunction "GND_2") (pintype "passive"))
      (node (ref "X1") (pin "GND@1") (pinfunction "GND4_GND@1") (pintype "power_in"))
      (node (ref "X1") (pin "GND@2") (pinfunction "GND3_GND@2") (pintype "power_in"))
      (node (ref "X1") (pin "GND@3") (pinfunction "GND2_GND@3") (pintype "power_in"))
      (node (ref "X1") (pin "GND@4") (pinfunction "GND1_GND@4") (pintype "power_in"))
      (node (ref "X2") (pin "GND@1") (pinfunction "GND4_GND@1") (pintype "power_in"))
      (node (ref "X2") (pin "GND@2") (pinfunction "GND3_GND@2") (pintype "power_in"))
      (node (ref "X2") (pin "GND@3") (pinfunction "GND2_GND@3") (pintype "power_in"))
      (node (ref "X2") (pin "GND@4") (pinfunction "GND1_GND@4") (pintype "power_in"))
      (node (ref "Y2") (pin "2") (pinfunction "GND_2") (pintype "power_in"))
      (node (ref "Y2") (pin "4") (pinfunction "GND_4") (pintype "power_in"))
    )
    (net (code "52") (name "Net-(BALUN1-BALANCED_PORT_1)") (class "Default")
      (node (ref "BALUN1") (pin "3") (pinfunction "BALANCED_PORT_1_3") (pintype "bidirectional"))
      (node (ref "C2") (pin "1") (pinfunction "1_1") (pintype "passive"))
    )
    (net (code "53") (name "Net-(BALUN1-BALANCED_PORT_2)") (class "Default")
      (node (ref "BALUN1") (pin "4") (pinfunction "BALANCED_PORT_2_4") (pintype "bidirectional"))
      (node (ref "C3") (pin "1") (pinfunction "1_1") (pintype "passive"))
    )
    (net (code "54") (name "Net-(BALUN1-UNBALANCED_PORT)") (class "Default")
      (node (ref "BALUN1") (pin "1") (pinfunction "UNBALANCED_PORT_1") (pintype "bidirectional"))
      (node (ref "X2") (pin "P") (pinfunction "ANT_P") (pintype "bidirectional"))
    )
    (net (code "55") (name "Net-(C5-Pad1)") (class "Default")
      (node (ref "C5") (pin "1") (pinfunction "1_1") (pintype "passive"))
      (node (ref "R2") (pin "1") (pinfunction "1_1") (pintype "passive"))
    )
    (net (code "56") (name "Net-(C8-Pad1)") (class "Default")
      (node (ref "C8") (pin "1") (pinfunction "1_1") (pintype "passive"))
      (node (ref "R3") (pin "1") (pinfunction "1_1") (pintype "passive"))
    )
    (net (code "57") (name "Net-(L1-Pad2)") (class "Default")
      (node (ref "L1") (pin "2") (pinfunction "2_2") (pintype "passive"))
      (node (ref "L2") (pin "1") (pinfunction "1_1") (pintype "passive"))
    )
    (net (code "58") (name "Net-(U1-CLKTUNE)") (class "Default")
      (node (ref "C6") (pin "1") (pinfunction "1_1") (pintype "passive"))
      (node (ref "R2") (pin "2") (pinfunction "2_2") (pintype "passive"))
      (node (ref "U1") (pin "8") (pinfunction "CLKTUNE_8") (pintype "bidirectional"))
    )
    (net (code "59") (name "Net-(U1-EXTCLK{slash}XTAL1)") (class "Default")
      (node (ref "C1") (pin "2") (pinfunction "2_2") (pintype "passive"))
      (node (ref "U1") (pin "3") (pinfunction "EXTCLK/XTAL1_3") (pintype "input"))
    )
    (net (code "60") (name "Net-(U1-VCOTUNE)") (class "Default")
      (node (ref "C9") (pin "1") (pinfunction "1_1") (pintype "passive"))
      (node (ref "R3") (pin "2") (pinfunction "2_2") (pintype "passive"))
      (node (ref "U1") (pin "12") (pinfunction "VCOTUNE_12") (pintype "bidirectional"))
    )
    (net (code "61") (name "Net-(U1-VDDDIG)") (class "Default")
      (node (ref "C19") (pin "1") (pinfunction "1_1") (pintype "passive"))
      (node (ref "C20") (pin "1") (pinfunction "1_1") (pintype "passive"))
      (node (ref "U1") (pin "20") (pinfunction "VDDREG_20") (pintype "power_in"))
      (node (ref "U1") (pin "44") (pinfunction "VDDDIG_44") (pintype "power_in"))
    )
    (net (code "62") (name "Net-(U1-VDDIF)") (class "Default")
      (node (ref "C12") (pin "1") (pinfunction "1_1") (pintype "passive"))
      (node (ref "U1") (pin "7") (pinfunction "VDDIF_7") (pintype "power_in"))
    )
    (net (code "63") (name "Net-(U1-VDDIO1)") (class "Default")
      (node (ref "C47") (pin "1") (pinfunction "1_1") (pintype "passive"))
      (node (ref "U1") (pin "31") (pinfunction "VDDIO1_31") (pintype "power_in"))
    )
    (net (code "64") (name "Net-(U1-VDDIO2)") (class "Default")
      (node (ref "C10") (pin "1") (pinfunction "1_1") (pintype "passive"))
      (node (ref "U1") (pin "42") (pinfunction "VDDIO2_42") (pintype "bidirectional"))
    )
    (net (code "65") (name "Net-(U1-VDDMS)") (class "Default")
      (node (ref "C11") (pin "1") (pinfunction "1_1") (pintype "passive"))
      (node (ref "U1") (pin "6") (pinfunction "VDDMS_6") (pintype "power_in"))
    )
    (net (code "66") (name "Net-(U1-VDDSYN)") (class "Default")
      (node (ref "C13") (pin "1") (pinfunction "1_1") (pintype "passive"))
      (node (ref "U1") (pin "10") (pinfunction "VDDSYN_10") (pintype "power_in"))
    )
    (net (code "67") (name "Net-(U1-VREF)") (class "Default")
      (node (ref "R1") (pin "2") (pinfunction "2_2") (pintype "passive"))
      (node (ref "U1") (pin "5") (pinfunction "VREF_5") (pintype "bidirectional"))
    )
    (net (code "68") (name "Net-(U2-DCC)") (class "Default")
      (node (ref "L2") (pin "2") (pinfunction "2_2") (pintype "passive"))
      (node (ref "U2") (pin "47") (pinfunction "DCC_47") (pintype "power_in"))
    )
    (net (code "69") (name "Net-(U2-DEC1)") (class "Default")
      (node (ref "C32") (pin "1") (pinfunction "1_1") (pintype "passive"))
      (node (ref "U2") (pin "1") (pinfunction "DEC1_1") (pintype "power_in"))
    )
    (net (code "70") (name "Net-(U2-DEC2)") (class "Default")
      (node (ref "C33") (pin "1") (pinfunction "1_1") (pintype "passive"))
      (node (ref "U2") (pin "32") (pinfunction "DEC2_32") (pintype "power_in"))
    )
    (net (code "71") (name "Net-(U2-DEC3)") (class "Default")
      (node (ref "C34") (pin "1") (pinfunction "1_1") (pintype "passive"))
      (node (ref "U2") (pin "33") (pinfunction "DEC3_33") (pintype "power_in"))
    )
    (net (code "72") (name "Net-(U2-DEC4)") (class "Default")
      (node (ref "C35") (pin "1") (pinfunction "1_1") (pintype "passive"))
      (node (ref "L1") (pin "1") (pinfunction "1_1") (pintype "passive"))
      (node (ref "U2") (pin "46") (pinfunction "DEC4_46") (pintype "power_in"))
    )
    (net (code "73") (name "Net-(U3-FB)") (class "Default")
      (node (ref "C43") (pin "1") (pinfunction "1_1") (pintype "passive"))
      (node (ref "L3") (pin "2") (pinfunction "2_2") (pintype "passive"))
      (node (ref "L4") (pin "1") (pinfunction "1_1") (pintype "passive"))
      (node (ref "U3") (pin "4") (pinfunction "FB_4") (pintype "passive"))
    )
    (net (code "74") (name "Net-(U3-SW)") (class "Default")
      (node (ref "L3") (pin "1") (pinfunction "1_1") (pintype "passive"))
      (node (ref "U3") (pin "5") (pinfunction "SW_5") (pintype "output"))
    )
    (net (code "75") (name "Net-(X1-ANT)") (class "Default")
      (node (ref "C1") (pin "1") (pinfunction "1_1") (pintype "passive"))
      (node (ref "X1") (pin "P") (pinfunction "ANT_P") (pintype "bidirectional"))
    )
    (net (code "76") (name "unconnected-(U1-GPIO4{slash}EXTPA-Pad34)") (class "Default")
      (node (ref "U1") (pin "34") (pinfunction "GPIO4/EXTPA_34") (pintype "bidirectional"))
    )
    (net (code "77") (name "unconnected-(U1-GPIO5{slash}EXTTXE{slash}SPIPOL-Pad33)") (class "Default")
      (node (ref "U1") (pin "33") (pinfunction "GPIO5/EXTTXE/SPIPOL_33") (pintype "bidirectional"))
    )
    (net (code "78") (name "unconnected-(U1-GPIO6{slash}EXTRXE{slash}SPIPHA-Pad30)") (class "Default")
      (node (ref "U1") (pin "30") (pinfunction "GPIO6/EXTRXE/SPIPHA_30") (pintype "bidirectional"))
    )
    (net (code "79") (name "unconnected-(U1-XTAL2-Pad4)") (class "Default")
      (node (ref "U1") (pin "4") (pinfunction "XTAL2_4") (pintype "input"))
    )
    (net (code "80") (name "unconnected-(U2-ANT-Pad30)") (class "Default")
      (node (ref "U2") (pin "30") (pinfunction "ANT_30") (pintype "passive"))
    )
  )
)
